# mosfet_brd.net
KiCad netlist of a schematic drawn in EAGLE
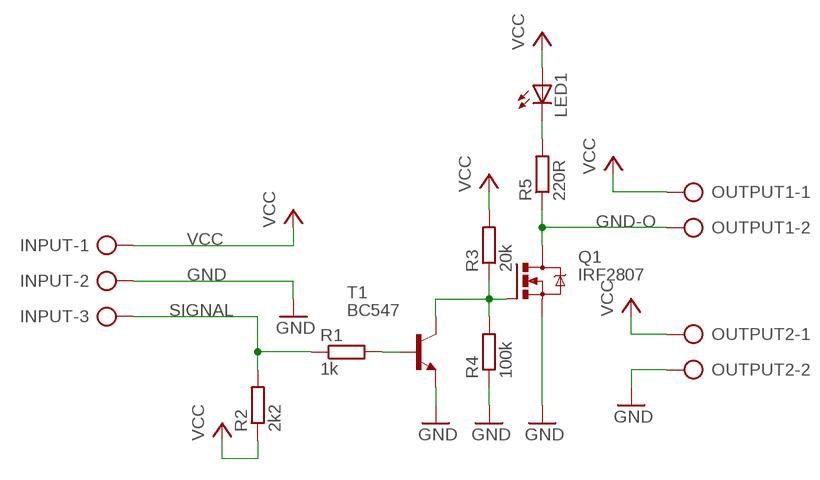
[diagram p0: schematic, sheet 1]

(export (version "E")
  (design (tool "Eeschema 10.0.6"))
  (components
    (comp (ref "INPUT")
      (value "AK300/3")
      (footprint "eagle-import:AK300_3")
      (libsource (lib "eagle-import") (part "AK300/3"))
    )
    (comp (ref "LED1")
      (value "LED3MM")
      (footprint "eagle-import:LED3MM")
      (libsource (lib "eagle-import") (part "LED3MM"))
    )
    (comp (ref "OUTPUT1")
      (value "AK300/2")
      (footprint "eagle-import:AK300_2")
      (libsource (lib "eagle-import") (part "AK300/2"))
    )
    (comp (ref "OUTPUT2")
      (value "AK300/2")
      (footprint "eagle-import:AK300_2")
      (libsource (lib "eagle-import") (part "AK300/2"))
    )
    (comp (ref "Q1")
      (value "IRF2807")
      (footprint "eagle-import:TO220BV")
      (libsource (lib "eagle-import") (part "IRF540"))
    )
    (comp (ref "R1")
      (value "1k")
      (footprint "eagle-import:0411_15")
      (libsource (lib "eagle-import") (part "R-EU_0411/15"))
    )
    (comp (ref "R2")
      (value "2k2")
      (footprint "eagle-import:0411_15")
      (libsource (lib "eagle-import") (part "R-EU_0411/15"))
    )
    (comp (ref "R3")
      (value "20k")
      (footprint "eagle-import:0411_15")
      (libsource (lib "eagle-import") (part "R-EU_0411/15"))
    )
    (comp (ref "R4")
      (value "100k")
      (footprint "eagle-import:0411_15")
      (libsource (lib "eagle-import") (part "R-EU_0411/15"))
    )
    (comp (ref "R5")
      (value "220R")
      (footprint "eagle-import:0411_15")
      (libsource (lib "eagle-import") (part "R-EU_0411/15"))
    )
    (comp (ref "T1")
      (value "BC547")
      (footprint "eagle-import:TO92-EBC")
      (libsource (lib "eagle-import") (part "BC548"))
    )
  )
  (nets
    (net (code "1") (name "/GND-O") (class "Default")
      (node (ref "OUTPUT1") (pin "2") (pinfunction "KL_2") (pintype "passive"))
      (node (ref "Q1") (pin "D") (pinfunction "D_D") (pintype "passive"))
      (node (ref "R5") (pin "1") (pinfunction "1_1") (pintype "passive"))
    )
    (net (code "2") (name "/SIGNAL") (class "Default")
      (node (ref "INPUT") (pin "3") (pinfunction "KL_3") (pintype "passive"))
      (node (ref "R1") (pin "1") (pinfunction "1_1") (pintype "passive"))
      (node (ref "R2") (pin "2") (pinfunction "2_2") (pintype "passive"))
    )
    (net (code "3") (name "GND") (class "Default")
      (node (ref "INPUT") (pin "2") (pinfunction "KL_2") (pintype "passive"))
      (node (ref "OUTPUT2") (pin "2") (pinfunction "KL_2") (pintype "passive"))
      (node (ref "Q1") (pin "S") (pinfunction "S_S") (pintype "passive"))
      (node (ref "R4") (pin "1") (pinfunction "1_1") (pintype "passive"))
      (node (ref "T1") (pin "E") (pinfunction "E_E") (pintype "passive"))
    )
    (net (code "4") (name "Net-(LED1-C)") (class "Default")
      (node (ref "LED1") (pin "K") (pinfunction "C_K") (pintype "passive"))
      (node (ref "R5") (pin "2") (pinfunction "2_2") (pintype "passive"))
    )
    (net (code "5") (name "Net-(Q1-PadG)") (class "Default")
      (node (ref "Q1") (pin "G") (pinfunction "G_G") (pintype "passive"))
      (node (ref "R3") (pin "1") (pinfunction "1_1") (pintype "passive"))
      (node (ref "R4") (pin "2") (pinfunction "2_2") (pintype "passive"))
      (node (ref "T1") (pin "C") (pinfunction "C_C") (pintype "passive"))
    )
    (net (code "6") (name "Net-(R1-Pad2)") (class "Default")
      (node (ref "R1") (pin "2") (pinfunction "2_2") (pintype "passive"))
      (node (ref "T1") (pin "B") (pinfunction "B_B") (pintype "passive"))
    )
    (net (code "7") (name "VCC") (class "Default")
      (node (ref "INPUT") (pin "1") (pinfunction "KL_1") (pintype "passive"))
      (node (ref "LED1") (pin "A") (pinfunction "A_A") (pintype "passive"))
      (node (ref "OUTPUT1") (pin "1") (pinfunction "KL_1") (pintype "passive"))
      (node (ref "OUTPUT2") (pin "1") (pinfunction "KL_1") (pintype "passive"))
      (node (ref "R2") (pin "1") (pinfunction "1_1") (pintype "passive"))
      (node (ref "R3") (pin "2") (pinfunction "2_2") (pintype "passive"))
    )
  )
)
